# cpu_board.net
KiCad netlist of a schematic drawn in EAGLE
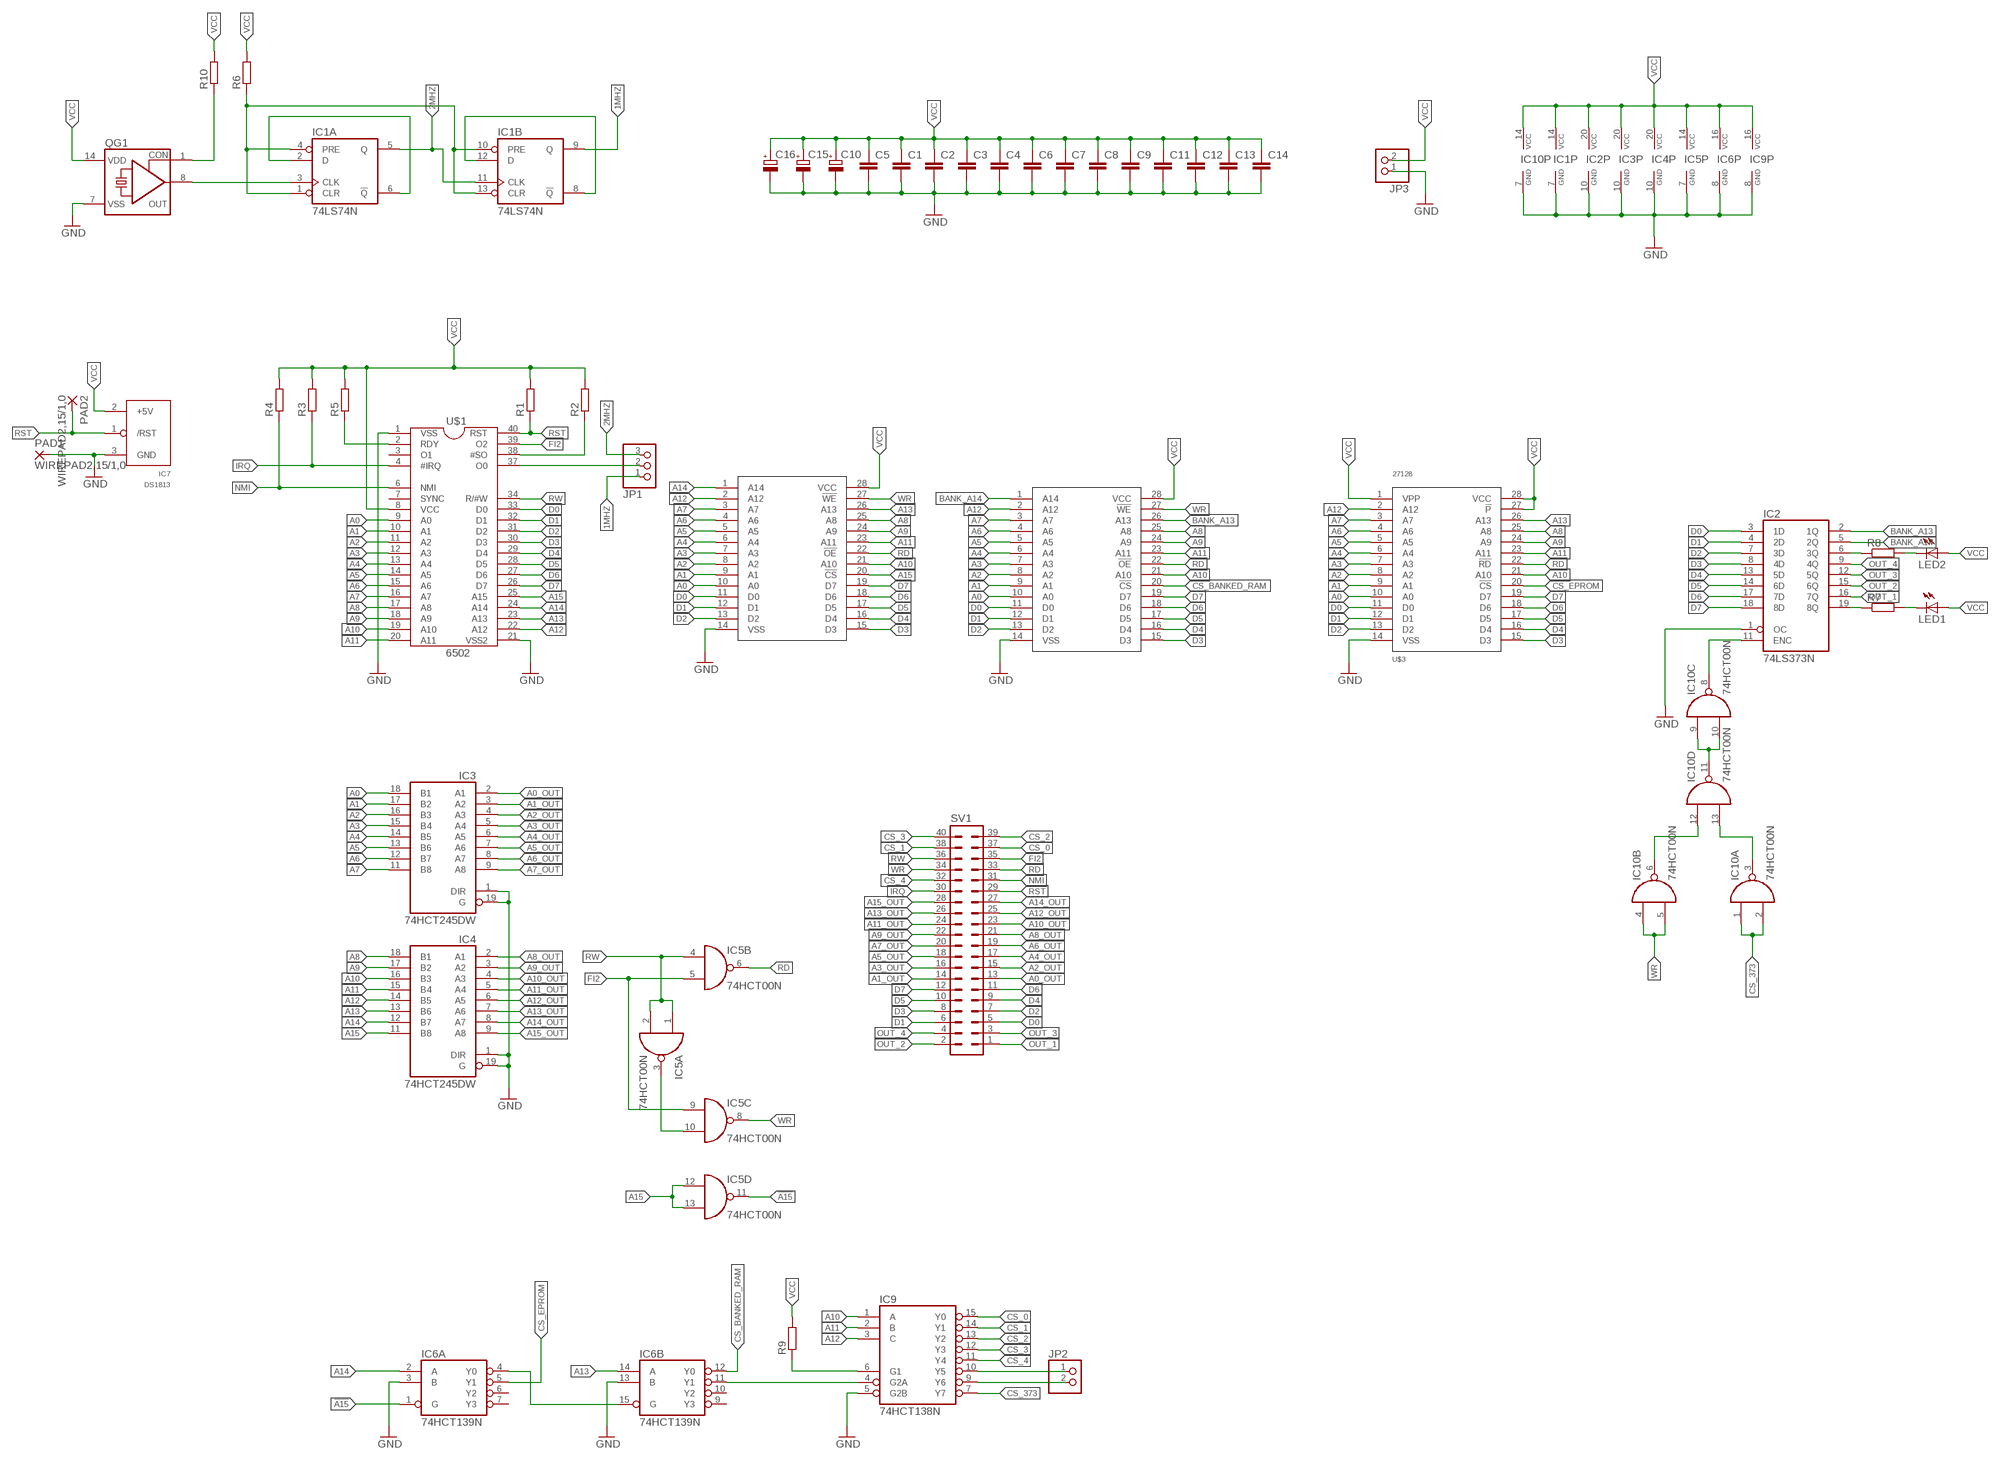
[diagram p0: schematic, sheet 1]

(export (version "E")
  (design (tool "Eeschema 10.0.6"))
  (components
    (comp (ref "C1")
      (value "C-EUC1206")
      (footprint "eagle-import:C1206")
      (libsource (lib "eagle-import") (part "C-EUC1206"))
    )
    (comp (ref "C2")
      (value "C-EUC1206")
      (footprint "eagle-import:C1206")
      (libsource (lib "eagle-import") (part "C-EUC1206"))
    )
    (comp (ref "C3")
      (value "C-EUC1206")
      (footprint "eagle-import:C1206")
      (libsource (lib "eagle-import") (part "C-EUC1206"))
    )
    (comp (ref "C4")
      (value "C-EUC1206")
      (footprint "eagle-import:C1206")
      (libsource (lib "eagle-import") (part "C-EUC1206"))
    )
    (comp (ref "C5")
      (value "C-EUC0603")
      (footprint "eagle-import:C0603")
      (libsource (lib "eagle-import") (part "C-EUC0603"))
    )
    (comp (ref "C6")
      (value "C-EUC1206")
      (footprint "eagle-import:C1206")
      (libsource (lib "eagle-import") (part "C-EUC1206"))
    )
    (comp (ref "C7")
      (value "C-EUC0603")
      (footprint "eagle-import:C0603")
      (libsource (lib "eagle-import") (part "C-EUC0603"))
    )
    (comp (ref "C8")
      (value "C-EUC1206")
      (footprint "eagle-import:C1206")
      (libsource (lib "eagle-import") (part "C-EUC1206"))
    )
    (comp (ref "C9")
      (value "C-EUC1206")
      (footprint "eagle-import:C1206")
      (libsource (lib "eagle-import") (part "C-EUC1206"))
    )
    (comp (ref "C10")
      (value "CPOL-EUE5-10.5")
      (footprint "eagle-import:E5-10,5")
      (libsource (lib "eagle-import") (part "CPOL-EUE5-10.5"))
    )
    (comp (ref "C11")
      (value "C-EUC0805")
      (footprint "eagle-import:C0805")
      (libsource (lib "eagle-import") (part "C-EUC0805"))
    )
    (comp (ref "C12")
      (value "C-EUC0805")
      (footprint "eagle-import:C0805")
      (libsource (lib "eagle-import") (part "C-EUC0805"))
    )
    (comp (ref "C13")
      (value "C-EUC0805")
      (footprint "eagle-import:C0805")
      (libsource (lib "eagle-import") (part "C-EUC0805"))
    )
    (comp (ref "C14")
      (value "C-EUC0603")
      (footprint "eagle-import:C0603")
      (libsource (lib "eagle-import") (part "C-EUC0603"))
    )
    (comp (ref "C15")
      (value "CPOL-EUSMCB")
      (footprint "eagle-import:SMC_B")
      (libsource (lib "eagle-import") (part "CPOL-EUSMCB"))
    )
    (comp (ref "C16")
      (value "CPOL-EUSMCB")
      (footprint "eagle-import:SMC_B")
      (libsource (lib "eagle-import") (part "CPOL-EUSMCB"))
    )
    (comp (ref "IC1")
      (value "74LS74N")
      (footprint "eagle-import:DIL14")
      (libsource (lib "eagle-import") (part "7474NLS"))
    )
    (comp (ref "IC2")
      (value "74LS373N")
      (footprint "eagle-import:DIL20")
      (libsource (lib "eagle-import") (part "74373NLS"))
    )
    (comp (ref "IC3")
      (value "74HCT245DW")
      (footprint "eagle-import:SO20W")
      (libsource (lib "eagle-import") (part "74245DWHCT"))
    )
    (comp (ref "IC4")
      (value "74HCT245DW")
      (footprint "eagle-import:SO20W")
      (libsource (lib "eagle-import") (part "74245DWHCT"))
    )
    (comp (ref "IC5")
      (value "74HCT00N")
      (footprint "eagle-import:DIL14")
      (libsource (lib "eagle-import") (part "7400NHCT"))
    )
    (comp (ref "IC6")
      (value "74HCT139N")
      (footprint "eagle-import:DIL16")
      (libsource (lib "eagle-import") (part "74139NHCT"))
    )
    (comp (ref "IC7")
      (value "DS1813")
      (footprint "eagle-import:TO-92")
      (libsource (lib "eagle-import") (part "DS1813"))
    )
    (comp (ref "IC9")
      (value "74HCT138N")
      (footprint "eagle-import:DIL16")
      (libsource (lib "eagle-import") (part "74138NHCT"))
    )
    (comp (ref "IC10")
      (value "74HCT00N")
      (footprint "eagle-import:DIL14")
      (libsource (lib "eagle-import") (part "7400NHCT"))
    )
    (comp (ref "JP1")
      (value "PINHD-1X3")
      (footprint "eagle-import:1X03")
      (libsource (lib "eagle-import") (part "PINHD-1X3"))
    )
    (comp (ref "JP2")
      (value "PINHD-1X2/90")
      (footprint "eagle-import:1X02_90")
      (libsource (lib "eagle-import") (part "PINHD-1X2/90"))
    )
    (comp (ref "JP3")
      (value "PINHD-1X2/90")
      (footprint "eagle-import:1X02_90")
      (libsource (lib "eagle-import") (part "PINHD-1X2/90"))
    )
    (comp (ref "LED1")
      (value "LED5MM")
      (footprint "eagle-import:LED5MM")
      (libsource (lib "eagle-import") (part "LED5MM"))
    )
    (comp (ref "LED2")
      (value "LED5MM")
      (footprint "eagle-import:LED5MM")
      (libsource (lib "eagle-import") (part "LED5MM"))
    )
    (comp (ref "PAD1")
      (value "WIREPAD2,15/1,0")
      (footprint "eagle-import:2,15_1,0")
      (libsource (lib "eagle-import") (part "WIREPAD2,15/1,0"))
    )
    (comp (ref "PAD2")
      (value "WIREPAD2,15/1,0")
      (footprint "eagle-import:2,15_1,0")
      (libsource (lib "eagle-import") (part "WIREPAD2,15/1,0"))
    )
    (comp (ref "QG1")
      (value "CRYSTAL_RES-SG51")
      (footprint "eagle-import:SG51")
      (libsource (lib "eagle-import") (part "CRYSTAL_RES-SG51"))
    )
    (comp (ref "R1")
      (value "R-EU_R1206")
      (footprint "eagle-import:R1206")
      (libsource (lib "eagle-import") (part "R-EU_R1206"))
    )
    (comp (ref "R2")
      (value "R-EU_R1206")
      (footprint "eagle-import:R1206")
      (libsource (lib "eagle-import") (part "R-EU_R1206"))
    )
    (comp (ref "R3")
      (value "R-EU_R1206")
      (footprint "eagle-import:R1206")
      (libsource (lib "eagle-import") (part "R-EU_R1206"))
    )
    (comp (ref "R4")
      (value "R-EU_R1206")
      (footprint "eagle-import:R1206")
      (libsource (lib "eagle-import") (part "R-EU_R1206"))
    )
    (comp (ref "R5")
      (value "R-EU_R1206")
      (footprint "eagle-import:R1206")
      (libsource (lib "eagle-import") (part "R-EU_R1206"))
    )
    (comp (ref "R6")
      (value "R-EU_M1206")
      (footprint "eagle-import:M1206")
      (libsource (lib "eagle-import") (part "R-EU_M1206"))
    )
    (comp (ref "R7")
      (value "R-EU_R1206")
      (footprint "eagle-import:R1206")
      (libsource (lib "eagle-import") (part "R-EU_R1206"))
    )
    (comp (ref "R8")
      (value "R-EU_R1206")
      (footprint "eagle-import:R1206")
      (libsource (lib "eagle-import") (part "R-EU_R1206"))
    )
    (comp (ref "R9")
      (value "R-EU_0204/7")
      (footprint "eagle-import:0204_7")
      (libsource (lib "eagle-import") (part "R-EU_0204/7"))
    )
    (comp (ref "R10")
      (value "R-EU_R1206")
      (footprint "eagle-import:R1206")
      (libsource (lib "eagle-import") (part "R-EU_R1206"))
    )
    (comp (ref "SV1")
      (value "ML40L")
      (footprint "eagle-import:ML40L")
      (libsource (lib "eagle-import") (part "ML40L"))
    )
    (comp (ref "U$1")
      (value "6502")
      (footprint "eagle-import:DIL40")
      (libsource (lib "eagle-import") (part "6502"))
    )
    (comp (ref "U$2")
      (value "62256")
      (footprint "eagle-import:DIL28-6")
      (libsource (lib "eagle-import") (part "62256"))
    )
    (comp (ref "U$3")
      (value "27128")
      (footprint "eagle-import:DIL28")
      (libsource (lib "eagle-import") (part "27128"))
    )
    (comp (ref "U$4")
      (value "62256")
      (footprint "eagle-import:DIL28-6")
      (libsource (lib "eagle-import") (part "62256"))
    )
  )
  (nets
    (net (code "1") (name "/~{A15}") (class "Default")
      (node (ref "IC5") (pin "11") (pinfunction "O_11") (pintype "output"))
      (node (ref "IC6") (pin "1") (pinfunction "G_1") (pintype "input"))
    )
    (net (code "2") (name "1MHZ") (class "Default")
      (node (ref "IC1") (pin "9") (pinfunction "Q_9") (pintype "output"))
      (node (ref "JP1") (pin "1") (pinfunction "1_1") (pintype "passive"))
    )
    (net (code "3") (name "2MHZ") (class "Default")
      (node (ref "IC1") (pin "11") (pinfunction "CLK_11") (pintype "input"))
      (node (ref "IC1") (pin "5") (pinfunction "Q_5") (pintype "output"))
      (node (ref "JP1") (pin "3") (pinfunction "3_3") (pintype "passive"))
    )
    (net (code "4") (name "A0") (class "Default")
      (node (ref "IC3") (pin "18") (pinfunction "B1_18") (pintype "bidirectional"))
      (node (ref "U$1") (pin "9") (pinfunction "A0_9") (pintype "bidirectional"))
      (node (ref "U$2") (pin "10") (pinfunction "A0_10") (pintype "bidirectional"))
      (node (ref "U$3") (pin "10") (pinfunction "A0_10") (pintype "bidirectional"))
      (node (ref "U$4") (pin "10") (pinfunction "A0_10") (pintype "bidirectional"))
    )
    (net (code "5") (name "A0_OUT") (class "Default")
      (node (ref "IC3") (pin "2") (pinfunction "A1_2") (pintype "bidirectional"))
      (node (ref "SV1") (pin "13") (pinfunction "13_13") (pintype "passive"))
    )
    (net (code "6") (name "A1") (class "Default")
      (node (ref "IC3") (pin "17") (pinfunction "B2_17") (pintype "bidirectional"))
      (node (ref "U$1") (pin "10") (pinfunction "A1_10") (pintype "bidirectional"))
      (node (ref "U$2") (pin "9") (pinfunction "A1_9") (pintype "bidirectional"))
      (node (ref "U$3") (pin "9") (pinfunction "A1_9") (pintype "bidirectional"))
      (node (ref "U$4") (pin "9") (pinfunction "A1_9") (pintype "bidirectional"))
    )
    (net (code "7") (name "A1_OUT") (class "Default")
      (node (ref "IC3") (pin "3") (pinfunction "A2_3") (pintype "bidirectional"))
      (node (ref "SV1") (pin "14") (pinfunction "14_14") (pintype "passive"))
    )
    (net (code "8") (name "A2") (class "Default")
      (node (ref "IC3") (pin "16") (pinfunction "B3_16") (pintype "bidirectional"))
      (node (ref "U$1") (pin "11") (pinfunction "A2_11") (pintype "bidirectional"))
      (node (ref "U$2") (pin "8") (pinfunction "A2_8") (pintype "bidirectional"))
      (node (ref "U$3") (pin "8") (pinfunction "A2_8") (pintype "bidirectional"))
      (node (ref "U$4") (pin "8") (pinfunction "A2_8") (pintype "bidirectional"))
    )
    (net (code "9") (name "A2_OUT") (class "Default")
      (node (ref "IC3") (pin "4") (pinfunction "A3_4") (pintype "bidirectional"))
      (node (ref "SV1") (pin "15") (pinfunction "15_15") (pintype "passive"))
    )
    (net (code "10") (name "A3") (class "Default")
      (node (ref "IC3") (pin "15") (pinfunction "B4_15") (pintype "bidirectional"))
      (node (ref "U$1") (pin "12") (pinfunction "A3_12") (pintype "bidirectional"))
      (node (ref "U$2") (pin "7") (pinfunction "A3_7") (pintype "bidirectional"))
      (node (ref "U$3") (pin "7") (pinfunction "A3_7") (pintype "bidirectional"))
      (node (ref "U$4") (pin "7") (pinfunction "A3_7") (pintype "bidirectional"))
    )
    (net (code "11") (name "A3_OUT") (class "Default")
      (node (ref "IC3") (pin "5") (pinfunction "A4_5") (pintype "bidirectional"))
      (node (ref "SV1") (pin "16") (pinfunction "16_16") (pintype "passive"))
    )
    (net (code "12") (name "A4") (class "Default")
      (node (ref "IC3") (pin "14") (pinfunction "B5_14") (pintype "bidirectional"))
      (node (ref "U$1") (pin "13") (pinfunction "A4_13") (pintype "bidirectional"))
      (node (ref "U$2") (pin "6") (pinfunction "A4_6") (pintype "bidirectional"))
      (node (ref "U$3") (pin "6") (pinfunction "A4_6") (pintype "bidirectional"))
      (node (ref "U$4") (pin "6") (pinfunction "A4_6") (pintype "bidirectional"))
    )
    (net (code "13") (name "A4_OUT") (class "Default")
      (node (ref "IC3") (pin "6") (pinfunction "A5_6") (pintype "bidirectional"))
      (node (ref "SV1") (pin "17") (pinfunction "17_17") (pintype "passive"))
    )
    (net (code "14") (name "A5") (class "Default")
      (node (ref "IC3") (pin "13") (pinfunction "B6_13") (pintype "bidirectional"))
      (node (ref "U$1") (pin "14") (pinfunction "A5_14") (pintype "bidirectional"))
      (node (ref "U$2") (pin "5") (pinfunction "A5_5") (pintype "bidirectional"))
      (node (ref "U$3") (pin "5") (pinfunction "A5_5") (pintype "bidirectional"))
      (node (ref "U$4") (pin "5") (pinfunction "A5_5") (pintype "bidirectional"))
    )
    (net (code "15") (name "A5_OUT") (class "Default")
      (node (ref "IC3") (pin "7") (pinfunction "A6_7") (pintype "bidirectional"))
      (node (ref "SV1") (pin "18") (pinfunction "18_18") (pintype "passive"))
    )
    (net (code "16") (name "A6") (class "Default")
      (node (ref "IC3") (pin "12") (pinfunction "B7_12") (pintype "bidirectional"))
      (node (ref "U$1") (pin "15") (pinfunction "A6_15") (pintype "bidirectional"))
      (node (ref "U$2") (pin "4") (pinfunction "A6_4") (pintype "bidirectional"))
      (node (ref "U$3") (pin "4") (pinfunction "A6_4") (pintype "bidirectional"))
      (node (ref "U$4") (pin "4") (pinfunction "A6_4") (pintype "bidirectional"))
    )
    (net (code "17") (name "A6_OUT") (class "Default")
      (node (ref "IC3") (pin "8") (pinfunction "A7_8") (pintype "bidirectional"))
      (node (ref "SV1") (pin "19") (pinfunction "19_19") (pintype "passive"))
    )
    (net (code "18") (name "A7") (class "Default")
      (node (ref "IC3") (pin "11") (pinfunction "B8_11") (pintype "bidirectional"))
      (node (ref "U$1") (pin "16") (pinfunction "A7_16") (pintype "bidirectional"))
      (node (ref "U$2") (pin "3") (pinfunction "A7_3") (pintype "bidirectional"))
      (node (ref "U$3") (pin "3") (pinfunction "A7_3") (pintype "bidirectional"))
      (node (ref "U$4") (pin "3") (pinfunction "A7_3") (pintype "bidirectional"))
    )
    (net (code "19") (name "A7_OUT") (class "Default")
      (node (ref "IC3") (pin "9") (pinfunction "A8_9") (pintype "bidirectional"))
      (node (ref "SV1") (pin "20") (pinfunction "20_20") (pintype "passive"))
    )
    (net (code "20") (name "A8") (class "Default")
      (node (ref "IC4") (pin "18") (pinfunction "B1_18") (pintype "bidirectional"))
      (node (ref "U$1") (pin "17") (pinfunction "A8_17") (pintype "bidirectional"))
      (node (ref "U$2") (pin "25") (pinfunction "A8_25") (pintype "bidirectional"))
      (node (ref "U$3") (pin "25") (pinfunction "A8_25") (pintype "bidirectional"))
      (node (ref "U$4") (pin "25") (pinfunction "A8_25") (pintype "bidirectional"))
    )
    (net (code "21") (name "A8_OUT") (class "Default")
      (node (ref "IC4") (pin "2") (pinfunction "A1_2") (pintype "bidirectional"))
      (node (ref "SV1") (pin "21") (pinfunction "21_21") (pintype "passive"))
    )
    (net (code "22") (name "A9") (class "Default")
      (node (ref "IC4") (pin "17") (pinfunction "B2_17") (pintype "bidirectional"))
      (node (ref "U$1") (pin "18") (pinfunction "A9_18") (pintype "bidirectional"))
      (node (ref "U$2") (pin "24") (pinfunction "A9_24") (pintype "bidirectional"))
      (node (ref "U$3") (pin "24") (pinfunction "A9_24") (pintype "bidirectional"))
      (node (ref "U$4") (pin "24") (pinfunction "A9_24") (pintype "bidirectional"))
    )
    (net (code "23") (name "A9_OUT") (class "Default")
      (node (ref "IC4") (pin "3") (pinfunction "A2_3") (pintype "bidirectional"))
      (node (ref "SV1") (pin "22") (pinfunction "22_22") (pintype "passive"))
    )
    (net (code "24") (name "A10") (class "Default")
      (node (ref "IC4") (pin "16") (pinfunction "B3_16") (pintype "bidirectional"))
      (node (ref "IC9") (pin "1") (pinfunction "A_1") (pintype "input"))
      (node (ref "U$1") (pin "19") (pinfunction "A10_19") (pintype "bidirectional"))
      (node (ref "U$2") (pin "21") (pinfunction "A10_21") (pintype "bidirectional"))
      (node (ref "U$3") (pin "21") (pinfunction "A10_21") (pintype "bidirectional"))
      (node (ref "U$4") (pin "21") (pinfunction "A10_21") (pintype "bidirectional"))
    )
    (net (code "25") (name "A10_OUT") (class "Default")
      (node (ref "IC4") (pin "4") (pinfunction "A3_4") (pintype "bidirectional"))
      (node (ref "SV1") (pin "23") (pinfunction "23_23") (pintype "passive"))
    )
    (net (code "26") (name "A11") (class "Default")
      (node (ref "IC4") (pin "15") (pinfunction "B4_15") (pintype "bidirectional"))
      (node (ref "IC9") (pin "2") (pinfunction "B_2") (pintype "input"))
      (node (ref "U$1") (pin "20") (pinfunction "A11_20") (pintype "bidirectional"))
      (node (ref "U$2") (pin "23") (pinfunction "A11_23") (pintype "bidirectional"))
      (node (ref "U$3") (pin "23") (pinfunction "A11_23") (pintype "bidirectional"))
      (node (ref "U$4") (pin "23") (pinfunction "A11_23") (pintype "bidirectional"))
    )
    (net (code "27") (name "A11_OUT") (class "Default")
      (node (ref "IC4") (pin "5") (pinfunction "A4_5") (pintype "bidirectional"))
      (node (ref "SV1") (pin "24") (pinfunction "24_24") (pintype "passive"))
    )
    (net (code "28") (name "A12") (class "Default")
      (node (ref "IC4") (pin "14") (pinfunction "B5_14") (pintype "bidirectional"))
      (node (ref "IC9") (pin "3") (pinfunction "C_3") (pintype "input"))
      (node (ref "U$1") (pin "22") (pinfunction "A12_22") (pintype "bidirectional"))
      (node (ref "U$2") (pin "2") (pinfunction "A12_2") (pintype "bidirectional"))
      (node (ref "U$3") (pin "2") (pinfunction "A12_2") (pintype "bidirectional"))
      (node (ref "U$4") (pin "2") (pinfunction "A12_2") (pintype "bidirectional"))
    )
    (net (code "29") (name "A12_OUT") (class "Default")
      (node (ref "IC4") (pin "6") (pinfunction "A5_6") (pintype "bidirectional"))
      (node (ref "SV1") (pin "25") (pinfunction "25_25") (pintype "passive"))
    )
    (net (code "30") (name "A13") (class "Default")
      (node (ref "IC4") (pin "13") (pinfunction "B6_13") (pintype "bidirectional"))
      (node (ref "IC6") (pin "14") (pinfunction "A_14") (pintype "input"))
      (node (ref "U$1") (pin "23") (pinfunction "A13_23") (pintype "bidirectional"))
      (node (ref "U$3") (pin "26") (pinfunction "A13_26") (pintype "bidirectional"))
      (node (ref "U$4") (pin "26") (pinfunction "A13_26") (pintype "bidirectional"))
    )
    (net (code "31") (name "A13_OUT") (class "Default")
      (node (ref "IC4") (pin "7") (pinfunction "A6_7") (pintype "bidirectional"))
      (node (ref "SV1") (pin "26") (pinfunction "26_26") (pintype "passive"))
    )
    (net (code "32") (name "A14") (class "Default")
      (node (ref "IC4") (pin "12") (pinfunction "B7_12") (pintype "bidirectional"))
      (node (ref "IC6") (pin "2") (pinfunction "A_2") (pintype "input"))
      (node (ref "U$1") (pin "24") (pinfunction "A14_24") (pintype "bidirectional"))
      (node (ref "U$4") (pin "1") (pinfunction "A14_1") (pintype "bidirectional"))
    )
    (net (code "33") (name "A14_OUT") (class "Default")
      (node (ref "IC4") (pin "8") (pinfunction "A7_8") (pintype "bidirectional"))
      (node (ref "SV1") (pin "27") (pinfunction "27_27") (pintype "passive"))
    )
    (net (code "34") (name "A15") (class "Default")
      (node (ref "IC4") (pin "11") (pinfunction "B8_11") (pintype "bidirectional"))
      (node (ref "IC5") (pin "12") (pinfunction "I0_12") (pintype "input"))
      (node (ref "IC5") (pin "13") (pinfunction "I1_13") (pintype "input"))
      (node (ref "U$1") (pin "25") (pinfunction "A15_25") (pintype "bidirectional"))
      (node (ref "U$4") (pin "20") (pinfunction "~{CS}_20") (pintype "bidirectional"))
    )
    (net (code "35") (name "A15_OUT") (class "Default")
      (node (ref "IC4") (pin "9") (pinfunction "A8_9") (pintype "bidirectional"))
      (node (ref "SV1") (pin "28") (pinfunction "28_28") (pintype "passive"))
    )
    (net (code "36") (name "BANK_A13") (class "Default")
      (node (ref "IC2") (pin "2") (pinfunction "1Q_2") (pintype "tri_state"))
      (node (ref "U$2") (pin "26") (pinfunction "A13_26") (pintype "bidirectional"))
    )
    (net (code "37") (name "BANK_A14") (class "Default")
      (node (ref "IC2") (pin "5") (pinfunction "2Q_5") (pintype "tri_state"))
      (node (ref "U$2") (pin "1") (pinfunction "A14_1") (pintype "bidirectional"))
    )
    (net (code "38") (name "CS_0") (class "Default")
      (node (ref "IC9") (pin "15") (pinfunction "Y0_15") (pintype "output"))
      (node (ref "SV1") (pin "37") (pinfunction "37_37") (pintype "passive"))
    )
    (net (code "39") (name "CS_1") (class "Default")
      (node (ref "IC9") (pin "14") (pinfunction "Y1_14") (pintype "output"))
      (node (ref "SV1") (pin "38") (pinfunction "38_38") (pintype "passive"))
    )
    (net (code "40") (name "CS_2") (class "Default")
      (node (ref "IC9") (pin "13") (pinfunction "Y2_13") (pintype "output"))
      (node (ref "SV1") (pin "39") (pinfunction "39_39") (pintype "passive"))
    )
    (net (code "41") (name "CS_3") (class "Default")
      (node (ref "IC9") (pin "12") (pinfunction "Y3_12") (pintype "output"))
      (node (ref "SV1") (pin "40") (pinfunction "40_40") (pintype "passive"))
    )
    (net (code "42") (name "CS_4") (class "Default")
      (node (ref "IC9") (pin "11") (pinfunction "Y4_11") (pintype "output"))
      (node (ref "SV1") (pin "32") (pinfunction "32_32") (pintype "passive"))
    )
    (net (code "43") (name "CS_373") (class "Default")
      (node (ref "IC10") (pin "1") (pinfunction "I0_1") (pintype "input"))
      (node (ref "IC10") (pin "2") (pinfunction "I1_2") (pintype "input"))
      (node (ref "IC9") (pin "7") (pinfunction "Y7_7") (pintype "output"))
    )
    (net (code "44") (name "CS_BANKED_RAM") (class "Default")
      (node (ref "IC6") (pin "12") (pinfunction "Y0_12") (pintype "output"))
      (node (ref "U$2") (pin "20") (pinfunction "~{CS}_20") (pintype "bidirectional"))
    )
    (net (code "45") (name "CS_EPROM") (class "Default")
      (node (ref "IC6") (pin "5") (pinfunction "Y1_5") (pintype "output"))
      (node (ref "U$3") (pin "20") (pinfunction "~{CS}_20") (pintype "bidirectional"))
    )
    (net (code "46") (name "D0") (class "Default")
      (node (ref "IC2") (pin "3") (pinfunction "1D_3") (pintype "input"))
      (node (ref "SV1") (pin "5") (pinfunction "5_5") (pintype "passive"))
      (node (ref "U$1") (pin "33") (pinfunction "D0_33") (pintype "bidirectional"))
      (node (ref "U$2") (pin "11") (pinfunction "D0_11") (pintype "bidirectional"))
      (node (ref "U$3") (pin "11") (pinfunction "D0_11") (pintype "bidirectional"))
      (node (ref "U$4") (pin "11") (pinfunction "D0_11") (pintype "bidirectional"))
    )
    (net (code "47") (name "D1") (class "Default")
      (node (ref "IC2") (pin "4") (pinfunction "2D_4") (pintype "input"))
      (node (ref "SV1") (pin "6") (pinfunction "6_6") (pintype "passive"))
      (node (ref "U$1") (pin "32") (pinfunction "D1_32") (pintype "bidirectional"))
      (node (ref "U$2") (pin "12") (pinfunction "D1_12") (pintype "bidirectional"))
      (node (ref "U$3") (pin "12") (pinfunction "D1_12") (pintype "bidirectional"))
      (node (ref "U$4") (pin "12") (pinfunction "D1_12") (pintype "bidirectional"))
    )
    (net (code "48") (name "D2") (class "Default")
      (node (ref "IC2") (pin "7") (pinfunction "3D_7") (pintype "input"))
      (node (ref "SV1") (pin "7") (pinfunction "7_7") (pintype "passive"))
      (node (ref "U$1") (pin "31") (pinfunction "D2_31") (pintype "bidirectional"))
      (node (ref "U$2") (pin "13") (pinfunction "D2_13") (pintype "bidirectional"))
      (node (ref "U$3") (pin "13") (pinfunction "D2_13") (pintype "bidirectional"))
      (node (ref "U$4") (pin "13") (pinfunction "D2_13") (pintype "bidirectional"))
    )
    (net (code "49") (name "D3") (class "Default")
      (node (ref "IC2") (pin "8") (pinfunction "4D_8") (pintype "input"))
      (node (ref "SV1") (pin "8") (pinfunction "8_8") (pintype "passive"))
      (node (ref "U$1") (pin "30") (pinfunction "D3_30") (pintype "bidirectional"))
      (node (ref "U$2") (pin "15") (pinfunction "D3_15") (pintype "bidirectional"))
      (node (ref "U$3") (pin "15") (pinfunction "D3_15") (pintype "bidirectional"))
      (node (ref "U$4") (pin "15") (pinfunction "D3_15") (pintype "bidirectional"))
    )
    (net (code "50") (name "D4") (class "Default")
      (node (ref "IC2") (pin "13") (pinfunction "5D_13") (pintype "input"))
      (node (ref "SV1") (pin "9") (pinfunction "9_9") (pintype "passive"))
      (node (ref "U$1") (pin "29") (pinfunction "D4_29") (pintype "bidirectional"))
      (node (ref "U$2") (pin "16") (pinfunction "D4_16") (pintype "bidirectional"))
      (node (ref "U$3") (pin "16") (pinfunction "D4_16") (pintype "bidirectional"))
      (node (ref "U$4") (pin "16") (pinfunction "D4_16") (pintype "bidirectional"))
    )
    (net (code "51") (name "D5") (class "Default")
      (node (ref "IC2") (pin "14") (pinfunction "6D_14") (pintype "input"))
      (node (ref "SV1") (pin "10") (pinfunction "10_10") (pintype "passive"))
      (node (ref "U$1") (pin "28") (pinfunction "D5_28") (pintype "bidirectional"))
      (node (ref "U$2") (pin "17") (pinfunction "D5_17") (pintype "bidirectional"))
      (node (ref "U$3") (pin "17") (pinfunction "D5_17") (pintype "bidirectional"))
      (node (ref "U$4") (pin "17") (pinfunction "D5_17") (pintype "bidirectional"))
    )
    (net (code "52") (name "D6") (class "Default")
      (node (ref "IC2") (pin "17") (pinfunction "7D_17") (pintype "input"))
      (node (ref "SV1") (pin "11") (pinfunction "11_11") (pintype "passive"))
      (node (ref "U$1") (pin "27") (pinfunction "D6_27") (pintype "bidirectional"))
      (node (ref "U$2") (pin "18") (pinfunction "D6_18") (pintype "bidirectional"))
      (node (ref "U$3") (pin "18") (pinfunction "D6_18") (pintype "bidirectional"))
      (node (ref "U$4") (pin "18") (pinfunction "D6_18") (pintype "bidirectional"))
    )
    (net (code "53") (name "D7") (class "Default")
      (node (ref "IC2") (pin "18") (pinfunction "8D_18") (pintype "input"))
      (node (ref "SV1") (pin "12") (pinfunction "12_12") (pintype "passive"))
      (node (ref "U$1") (pin "26") (pinfunction "D7_26") (pintype "bidirectional"))
      (node (ref "U$2") (pin "19") (pinfunction "D7_19") (pintype "bidirectional"))
      (node (ref "U$3") (pin "19") (pinfunction "D7_19") (pintype "bidirectional"))
      (node (ref "U$4") (pin "19") (pinfunction "D7_19") (pintype "bidirectional"))
    )
    (net (code "54") (name "FI2") (class "Default")
      (node (ref "IC5") (pin "5") (pinfunction "I1_5") (pintype "input"))
      (node (ref "IC5") (pin "9") (pinfunction "I0_9") (pintype "input"))
      (node (ref "SV1") (pin "35") (pinfunction "35_35") (pintype "passive"))
      (node (ref "U$1") (pin "39") (pinfunction "O2_39") (pintype "bidirectional"))
    )
    (net (code "55") (name "GND") (class "Default")
      (node (ref "C1") (pin "2") (pinfunction "2_2") (pintype "passive"))
      (node (ref "C10") (pin "-") (pinfunction "-_-") (pintype "passive"))
      (node (ref "C11") (pin "2") (pinfunction "2_2") (pintype "passive"))
      (node (ref "C12") (pin "2") (pinfunction "2_2") (pintype "passive"))
      (node (ref "C13") (pin "2") (pinfunction "2_2") (pintype "passive"))
      (node (ref "C14") (pin "2") (pinfunction "2_2") (pintype "passive"))
      (node (ref "C15") (pin "-") (pinfunction "-_-") (pintype "passive"))
      (node (ref "C16") (pin "-") (pinfunction "-_-") (pintype "passive"))
      (node (ref "C2") (pin "2") (pinfunction "2_2") (pintype "passive"))
      (node (ref "C3") (pin "2") (pinfunction "2_2") (pintype "passive"))
      (node (ref "C4") (pin "2") (pinfunction "2_2") (pintype "passive"))
      (node (ref "C5") (pin "2") (pinfunction "2_2") (pintype "passive"))
      (node (ref "C6") (pin "2") (pinfunction "2_2") (pintype "passive"))
      (node (ref "C7") (pin "2") (pinfunction "2_2") (pintype "passive"))
      (node (ref "C8") (pin "2") (pinfunction "2_2") (pintype "passive"))
      (node (ref "C9") (pin "2") (pinfunction "2_2") (pintype "passive"))
      (node (ref "IC1") (pin "7") (pinfunction "GND_7") (pintype "power_in"))
      (node (ref "IC10") (pin "7") (pinfunction "GND_7") (pintype "power_in"))
      (node (ref "IC2") (pin "1") (pinfunction "OC_1") (pintype "input"))
      (node (ref "IC2") (pin "10") (pinfunction "GND_10") (pintype "power_in"))
      (node (ref "IC3") (pin "1") (pinfunction "DIR_1") (pintype "input"))
      (node (ref "IC3") (pin "10") (pinfunction "GND_10") (pintype "power_in"))
      (node (ref "IC3") (pin "19") (pinfunction "G_19") (pintype "input"))
      (node (ref "IC4") (pin "1") (pinfunction "DIR_1") (pintype "input"))
      (node (ref "IC4") (pin "10") (pinfunction "GND_10") (pintype "power_in"))
      (node (ref "IC4") (pin "19") (pinfunction "G_19") (pintype "input"))
      (node (ref "IC5") (pin "7") (pinfunction "GND_7") (pintype "power_in"))
      (node (ref "IC6") (pin "13") (pinfunction "B_13") (pintype "input"))
      (node (ref "IC6") (pin "3") (pinfunction "B_3") (pintype "input"))
      (node (ref "IC6") (pin "8") (pinfunction "GND_8") (pintype "power_in"))
      (node (ref "IC7") (pin "3") (pinfunction "GND_3") (pintype "power_in"))
      (node (ref "IC9") (pin "5") (pinfunction "G2B_5") (pintype "input"))
      (node (ref "IC9") (pin "8") (pinfunction "GND_8") (pintype "power_in"))
      (node (ref "JP3") (pin "1") (pinfunction "1_1") (pintype "passive"))
      (node (ref "PAD1") (pin "1") (pinfunction "P_1") (pintype "passive"))
      (node (ref "QG1") (pin "7") (pinfunction "VSS_7") (pintype "power_in"))
      (node (ref "U$1") (pin "1") (pinfunction "VSS_1") (pintype "bidirectional"))
      (node (ref "U$1") (pin "21") (pinfunction "VSS2_21") (pintype "bidirectional"))
      (node (ref "U$2") (pin "14") (pinfunction "VSS_14") (pintype "bidirectional"))
      (node (ref "U$3") (pin "14") (pinfunction "VSS_14") (pintype "bidirectional"))
      (node (ref "U$4") (pin "14") (pinfunction "VSS_14") (pintype "bidirectional"))
    )
    (net (code "56") (name "IRQ") (class "Default")
      (node (ref "R3") (pin "1") (pinfunction "1_1") (pintype "passive"))
      (node (ref "SV1") (pin "30") (pinfunction "30_30") (pintype "passive"))
      (node (ref "U$1") (pin "4") (pinfunction "#IRQ_4") (pintype "bidirectional"))
    )
    (net (code "57") (name "NMI") (class "Default")
      (node (ref "R4") (pin "1") (pinfunction "1_1") (pintype "passive"))
      (node (ref "SV1") (pin "31") (pinfunction "31_31") (pintype "passive"))
      (node (ref "U$1") (pin "6") (pinfunction "NMI_6") (pintype "bidirectional"))
    )
    (net (code "58") (name "Net-(IC1A-CLK)") (class "Default")
      (node (ref "IC1") (pin "3") (pinfunction "CLK_3") (pintype "input"))
      (node (ref "QG1") (pin "8") (pinfunction "OUT_8") (pintype "output"))
    )
    (net (code "59") (name "Net-(IC1A-CLR)") (class "Default")
      (node (ref "IC1") (pin "1") (pinfunction "CLR_1") (pintype "input"))
      (node (ref "IC1") (pin "10") (pinfunction "PRE_10") (pintype "input"))
      (node (ref "IC1") (pin "13") (pinfunction "CLR_13") (pintype "input"))
      (node (ref "IC1") (pin "4") (pinfunction "PRE_4") (pintype "input"))
      (node (ref "R6") (pin "1") (pinfunction "1_1") (pintype "passive"))
    )
    (net (code "60") (name "Net-(IC1A-D)") (class "Default")
      (node (ref "IC1") (pin "2") (pinfunction "D_2") (pintype "input"))
      (node (ref "IC1") (pin "6") (pinfunction "~{Q}_6") (pintype "output"))
    )
    (net (code "61") (name "Net-(IC1B-D)") (class "Default")
      (node (ref "IC1") (pin "12") (pinfunction "D_12") (pintype "input"))
      (node (ref "IC1") (pin "8") (pinfunction "~{Q}_8") (pintype "output"))
    )
    (net (code "62") (name "Net-(IC2A-3Q)") (class "Default")
      (node (ref "IC2") (pin "6") (pinfunction "3Q_6") (pintype "tri_state"))
      (node (ref "R8") (pin "1") (pinfunction "1_1") (pintype "passive"))
    )
    (net (code "63") (name "Net-(IC2A-8Q)") (class "Default")
      (node (ref "IC2") (pin "19") (pinfunction "8Q_19") (pintype "tri_state"))
      (node (ref "R7") (pin "1") (pinfunction "1_1") (pintype "passive"))
    )
    (net (code "64") (name "Net-(IC5A-O)") (class "Default")
      (node (ref "IC5") (pin "10") (pinfunction "I1_10") (pintype "input"))
      (node (ref "IC5") (pin "3") (pinfunction "O_3") (pintype "output"))
    )
    (net (code "65") (name "Net-(IC6A-Y0)") (class "Default")
      (node (ref "IC6") (pin "15") (pinfunction "G_15") (pintype "input"))
      (node (ref "IC6") (pin "4") (pinfunction "Y0_4") (pintype "output"))
    )
    (net (code "66") (name "Net-(IC6B-Y1)") (class "Default")
      (node (ref "IC6") (pin "11") (pinfunction "Y1_11") (pintype "output"))
      (node (ref "IC9") (pin "4") (pinfunction "G2A_4") (pintype "input"))
    )
    (net (code "67") (name "Net-(IC9A-G1)") (class "Default")
      (node (ref "IC9") (pin "6") (pinfunction "G1_6") (pintype "input"))
      (node (ref "R9") (pin "1") (pinfunction "1_1") (pintype "passive"))
    )
    (net (code "68") (name "Net-(IC9A-Y5)") (class "Default")
      (node (ref "IC9") (pin "10") (pinfunction "Y5_10") (pintype "output"))
      (node (ref "JP2") (pin "1") (pinfunction "1_1") (pintype "passive"))
    )
    (net (code "69") (name "Net-(IC9A-Y6)") (class "Default")
      (node (ref "IC9") (pin "9") (pinfunction "Y6_9") (pintype "output"))
      (node (ref "JP2") (pin "2") (pinfunction "2_2") (pintype "passive"))
    )
    (net (code "70") (name "Net-(IC10A-O)") (class "Default")
      (node (ref "IC10") (pin "13") (pinfunction "I1_13") (pintype "input"))
      (node (ref "IC10") (pin "3") (pinfunction "O_3") (pintype "output"))
    )
    (net (code "71") (name "Net-(IC10B-O)") (class "Default")
      (node (ref "IC10") (pin "12") (pinfunction "I0_12") (pintype "input"))
      (node (ref "IC10") (pin "6") (pinfunction "O_6") (pintype "output"))
    )
    (net (code "72") (name "Net-(IC10C-I0)") (class "Default")
      (node (ref "IC10") (pin "10") (pinfunction "I1_10") (pintype "input"))
      (node (ref "IC10") (pin "11") (pinfunction "O_11") (pintype "output"))
      (node (ref "IC10") (pin "9") (pinfunction "I0_9") (pintype "input"))
    )
    (net (code "73") (name "Net-(IC10C-O)") (class "Default")
      (node (ref "IC10") (pin "8") (pinfunction "O_8") (pintype "output"))
      (node (ref "IC2") (pin "11") (pinfunction "ENC_11") (pintype "input"))
    )
    (net (code "74") (name "Net-(LED1-C)") (class "Default")
      (node (ref "LED1") (pin "K") (pinfunction "C_K") (pintype "passive"))
      (node (ref "R7") (pin "2") (pinfunction "2_2") (pintype "passive"))
    )
    (net (code "75") (name "Net-(LED2-C)") (class "Default")
      (node (ref "LED2") (pin "K") (pinfunction "C_K") (pintype "passive"))
      (node (ref "R8") (pin "2") (pinfunction "2_2") (pintype "passive"))
    )
    (net (code "76") (name "Net-(QG1-CON)") (class "Default")
      (node (ref "QG1") (pin "1") (pinfunction "CON_1") (pintype "input"))
      (node (ref "R10") (pin "1") (pinfunction "1_1") (pintype "passive"))
    )
    (net (code "77") (name "Net-(U$1-#SO)") (class "Default")
      (node (ref "R2") (pin "1") (pinfunction "1_1") (pintype "passive"))
      (node (ref "U$1") (pin "38") (pinfunction "#SO_38") (pintype "bidirectional"))
    )
    (net (code "78") (name "Net-(U$1-O0)") (class "Default")
      (node (ref "JP1") (pin "2") (pinfunction "2_2") (pintype "passive"))
      (node (ref "U$1") (pin "37") (pinfunction "O0_37") (pintype "bidirectional"))
    )
    (net (code "79") (name "Net-(U$1-RDY)") (class "Default")
      (node (ref "R5") (pin "1") (pinfunction "1_1") (pintype "passive"))
      (node (ref "U$1") (pin "2") (pinfunction "RDY_2") (pintype "bidirectional"))
    )
    (net (code "80") (name "OUT_1") (class "Default")
      (node (ref "IC2") (pin "16") (pinfunction "7Q_16") (pintype "tri_state"))
      (node (ref "SV1") (pin "1") (pinfunction "1_1") (pintype "passive"))
    )
    (net (code "81") (name "OUT_2") (class "Default")
      (node (ref "IC2") (pin "15") (pinfunction "6Q_15") (pintype "tri_state"))
      (node (ref "SV1") (pin "2") (pinfunction "2_2") (pintype "passive"))
    )
    (net (code "82") (name "OUT_3") (class "Default")
      (node (ref "IC2") (pin "12") (pinfunction "5Q_12") (pintype "tri_state"))
      (node (ref "SV1") (pin "3") (pinfunction "3_3") (pintype "passive"))
    )
    (net (code "83") (name "OUT_4") (class "Default")
      (node (ref "IC2") (pin "9") (pinfunction "4Q_9") (pintype "tri_state"))
      (node (ref "SV1") (pin "4") (pinfunction "4_4") (pintype "passive"))
    )
    (net (code "84") (name "RD") (class "Default")
      (node (ref "IC5") (pin "6") (pinfunction "O_6") (pintype "output"))
      (node (ref "SV1") (pin "33") (pinfunction "33_33") (pintype "passive"))
      (node (ref "U$2") (pin "22") (pinfunction "~{OE}_22") (pintype "bidirectional"))
      (node (ref "U$3") (pin "22") (pinfunction "~{RD}_22") (pintype "bidirectional"))
      (node (ref "U$4") (pin "22") (pinfunction "~{OE}_22") (pintype "bidirectional"))
    )
    (net (code "85") (name "RST") (class "Default")
      (node (ref "IC7") (pin "1") (pinfunction "/RST_1") (pintype "passive"))
      (node (ref "PAD2") (pin "1") (pinfunction "P_1") (pintype "passive"))
      (node (ref "R1") (pin "1") (pinfunction "1_1") (pintype "passive"))
      (node (ref "SV1") (pin "29") (pinfunction "29_29") (pintype "passive"))
      (node (ref "U$1") (pin "40") (pinfunction "RST_40") (pintype "bidirectional"))
    )
    (net (code "86") (name "RW") (class "Default")
      (node (ref "IC5") (pin "1") (pinfunction "I0_1") (pintype "input"))
      (node (ref "IC5") (pin "2") (pinfunction "I1_2") (pintype "input"))
      (node (ref "IC5") (pin "4") (pinfunction "I0_4") (pintype "input"))
      (node (ref "SV1") (pin "36") (pinfunction "36_36") (pintype "passive"))
      (node (ref "U$1") (pin "34") (pinfunction "R/#W_34") (pintype "bidirectional"))
    )
    (net (code "87") (name "VCC") (class "Default")
      (node (ref "C1") (pin "1") (pinfunction "1_1") (pintype "passive"))
      (node (ref "C10") (pin "+") (pinfunction "+_+") (pintype "passive"))
      (node (ref "C11") (pin "1") (pinfunction "1_1") (pintype "passive"))
      (node (ref "C12") (pin "1") (pinfunction "1_1") (pintype "passive"))
      (node (ref "C13") (pin "1") (pinfunction "1_1") (pintype "passive"))
      (node (ref "C14") (pin "1") (pinfunction "1_1") (pintype "passive"))
      (node (ref "C15") (pin "+") (pinfunction "+_+") (pintype "passive"))
      (node (ref "C16") (pin "+") (pinfunction "+_+") (pintype "passive"))
      (node (ref "C2") (pin "1") (pinfunction "1_1") (pintype "passive"))
      (node (ref "C3") (pin "1") (pinfunction "1_1") (pintype "passive"))
      (node (ref "C4") (pin "1") (pinfunction "1_1") (pintype "passive"))
      (node (ref "C5") (pin "1") (pinfunction "1_1") (pintype "passive"))
      (node (ref "C6") (pin "1") (pinfunction "1_1") (pintype "passive"))
      (node (ref "C7") (pin "1") (pinfunction "1_1") (pintype "passive"))
      (node (ref "C8") (pin "1") (pinfunction "1_1") (pintype "passive"))
      (node (ref "C9") (pin "1") (pinfunction "1_1") (pintype "passive"))
      (node (ref "IC1") (pin "14") (pinfunction "VCC_14") (pintype "power_in"))
      (node (ref "IC10") (pin "14") (pinfunction "VCC_14") (pintype "power_in"))
      (node (ref "IC2") (pin "20") (pinfunction "VCC_20") (pintype "power_in"))
      (node (ref "IC3") (pin "20") (pinfunction "VCC_20") (pintype "power_in"))
      (node (ref "IC4") (pin "20") (pinfunction "VCC_20") (pintype "power_in"))
      (node (ref "IC5") (pin "14") (pinfunction "VCC_14") (pintype "power_in"))
      (node (ref "IC6") (pin "16") (pinfunction "VCC_16") (pintype "power_in"))
      (node (ref "IC7") (pin "2") (pinfunction "+5V_2") (pintype "power_in"))
      (node (ref "IC9") (pin "16") (pinfunction "VCC_16") (pintype "power_in"))
      (node (ref "JP3") (pin "2") (pinfunction "2_2") (pintype "passive"))
      (node (ref "LED1") (pin "A") (pinfunction "A_A") (pintype "passive"))
      (node (ref "LED2") (pin "A") (pinfunction "A_A") (pintype "passive"))
      (node (ref "QG1") (pin "14") (pinfunction "VDD_14") (pintype "power_in"))
      (node (ref "R1") (pin "2") (pinfunction "2_2") (pintype "passive"))
      (node (ref "R10") (pin "2") (pinfunction "2_2") (pintype "passive"))
      (node (ref "R2") (pin "2") (pinfunction "2_2") (pintype "passive"))
      (node (ref "R3") (pin "2") (pinfunction "2_2") (pintype "passive"))
      (node (ref "R4") (pin "2") (pinfunction "2_2") (pintype "passive"))
      (node (ref "R5") (pin "2") (pinfunction "2_2") (pintype "passive"))
      (node (ref "R6") (pin "2") (pinfunction "2_2") (pintype "passive"))
      (node (ref "R9") (pin "2") (pinfunction "2_2") (pintype "passive"))
      (node (ref "U$1") (pin "8") (pinfunction "VCC_8") (pintype "bidirectional"))
      (node (ref "U$2") (pin "28") (pinfunction "VCC_28") (pintype "bidirectional"))
      (node (ref "U$3") (pin "1") (pinfunction "VPP_1") (pintype "bidirectional"))
      (node (ref "U$3") (pin "27") (pinfunction "~{P}_27") (pintype "bidirectional"))
      (node (ref "U$3") (pin "28") (pinfunction "VCC_28") (pintype "bidirectional"))
      (node (ref "U$4") (pin "28") (pinfunction "VCC_28") (pintype "bidirectional"))
    )
    (net (code "88") (name "WR") (class "Default")
      (node (ref "IC10") (pin "4") (pinfunction "I0_4") (pintype "input"))
      (node (ref "IC10") (pin "5") (pinfunction "I1_5") (pintype "input"))
      (node (ref "IC5") (pin "8") (pinfunction "O_8") (pintype "output"))
      (node (ref "SV1") (pin "34") (pinfunction "34_34") (pintype "passive"))
      (node (ref "U$2") (pin "27") (pinfunction "~{WE}_27") (pintype "bidirectional"))
      (node (ref "U$4") (pin "27") (pinfunction "~{WE}_27") (pintype "bidirectional"))
    )
    (net (code "89") (name "unconnected-(IC6A-Y2-Pad6)") (class "Default")
      (node (ref "IC6") (pin "6") (pinfunction "Y2_6") (pintype "output"))
    )
    (net (code "90") (name "unconnected-(IC6A-Y3-Pad7)") (class "Default")
      (node (ref "IC6") (pin "7") (pinfunction "Y3_7") (pintype "output"))
    )
    (net (code "91") (name "unconnected-(IC6B-Y2-Pad10)") (class "Default")
      (node (ref "IC6") (pin "10") (pinfunction "Y2_10") (pintype "output"))
    )
    (net (code "92") (name "unconnected-(IC6B-Y3-Pad9)") (class "Default")
      (node (ref "IC6") (pin "9") (pinfunction "Y3_9") (pintype "output"))
    )
    (net (code "93") (name "unconnected-(U$1-O1-Pad3)") (class "Default")
      (node (ref "U$1") (pin "3") (pinfunction "O1_3") (pintype "bidirectional"))
    )
    (net (code "94") (name "unconnected-(U$1-SYNC-Pad7)") (class "Default")
      (node (ref "U$1") (pin "7") (pinfunction "SYNC_7") (pintype "bidirectional"))
    )
  )
)
